# InkTime.net
KiCad netlist of a schematic drawn in EAGLE
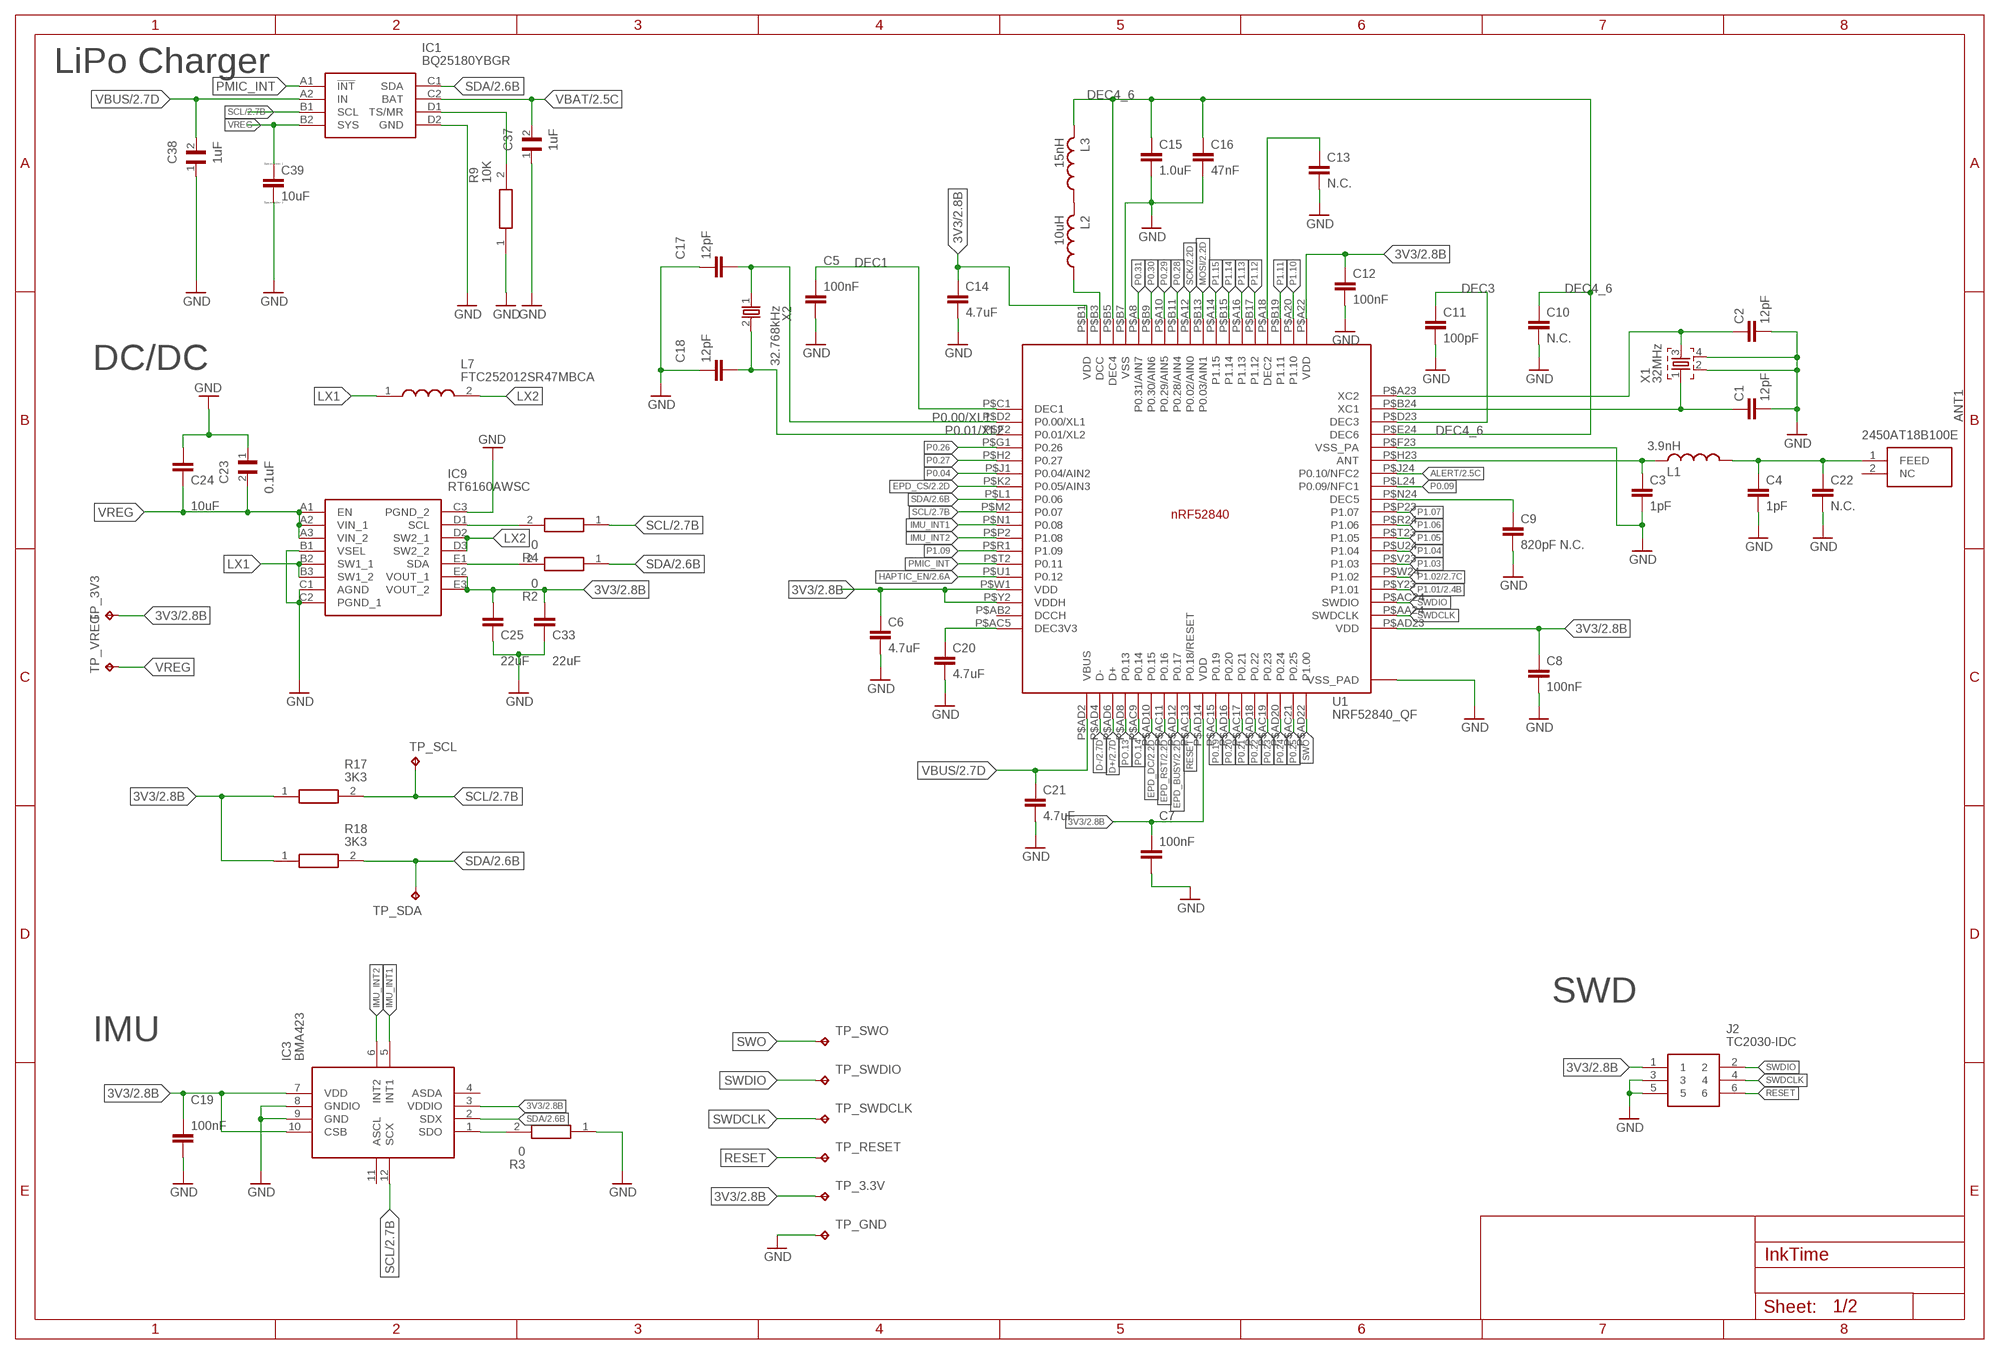
[diagram p0: schematic, sheet 1]
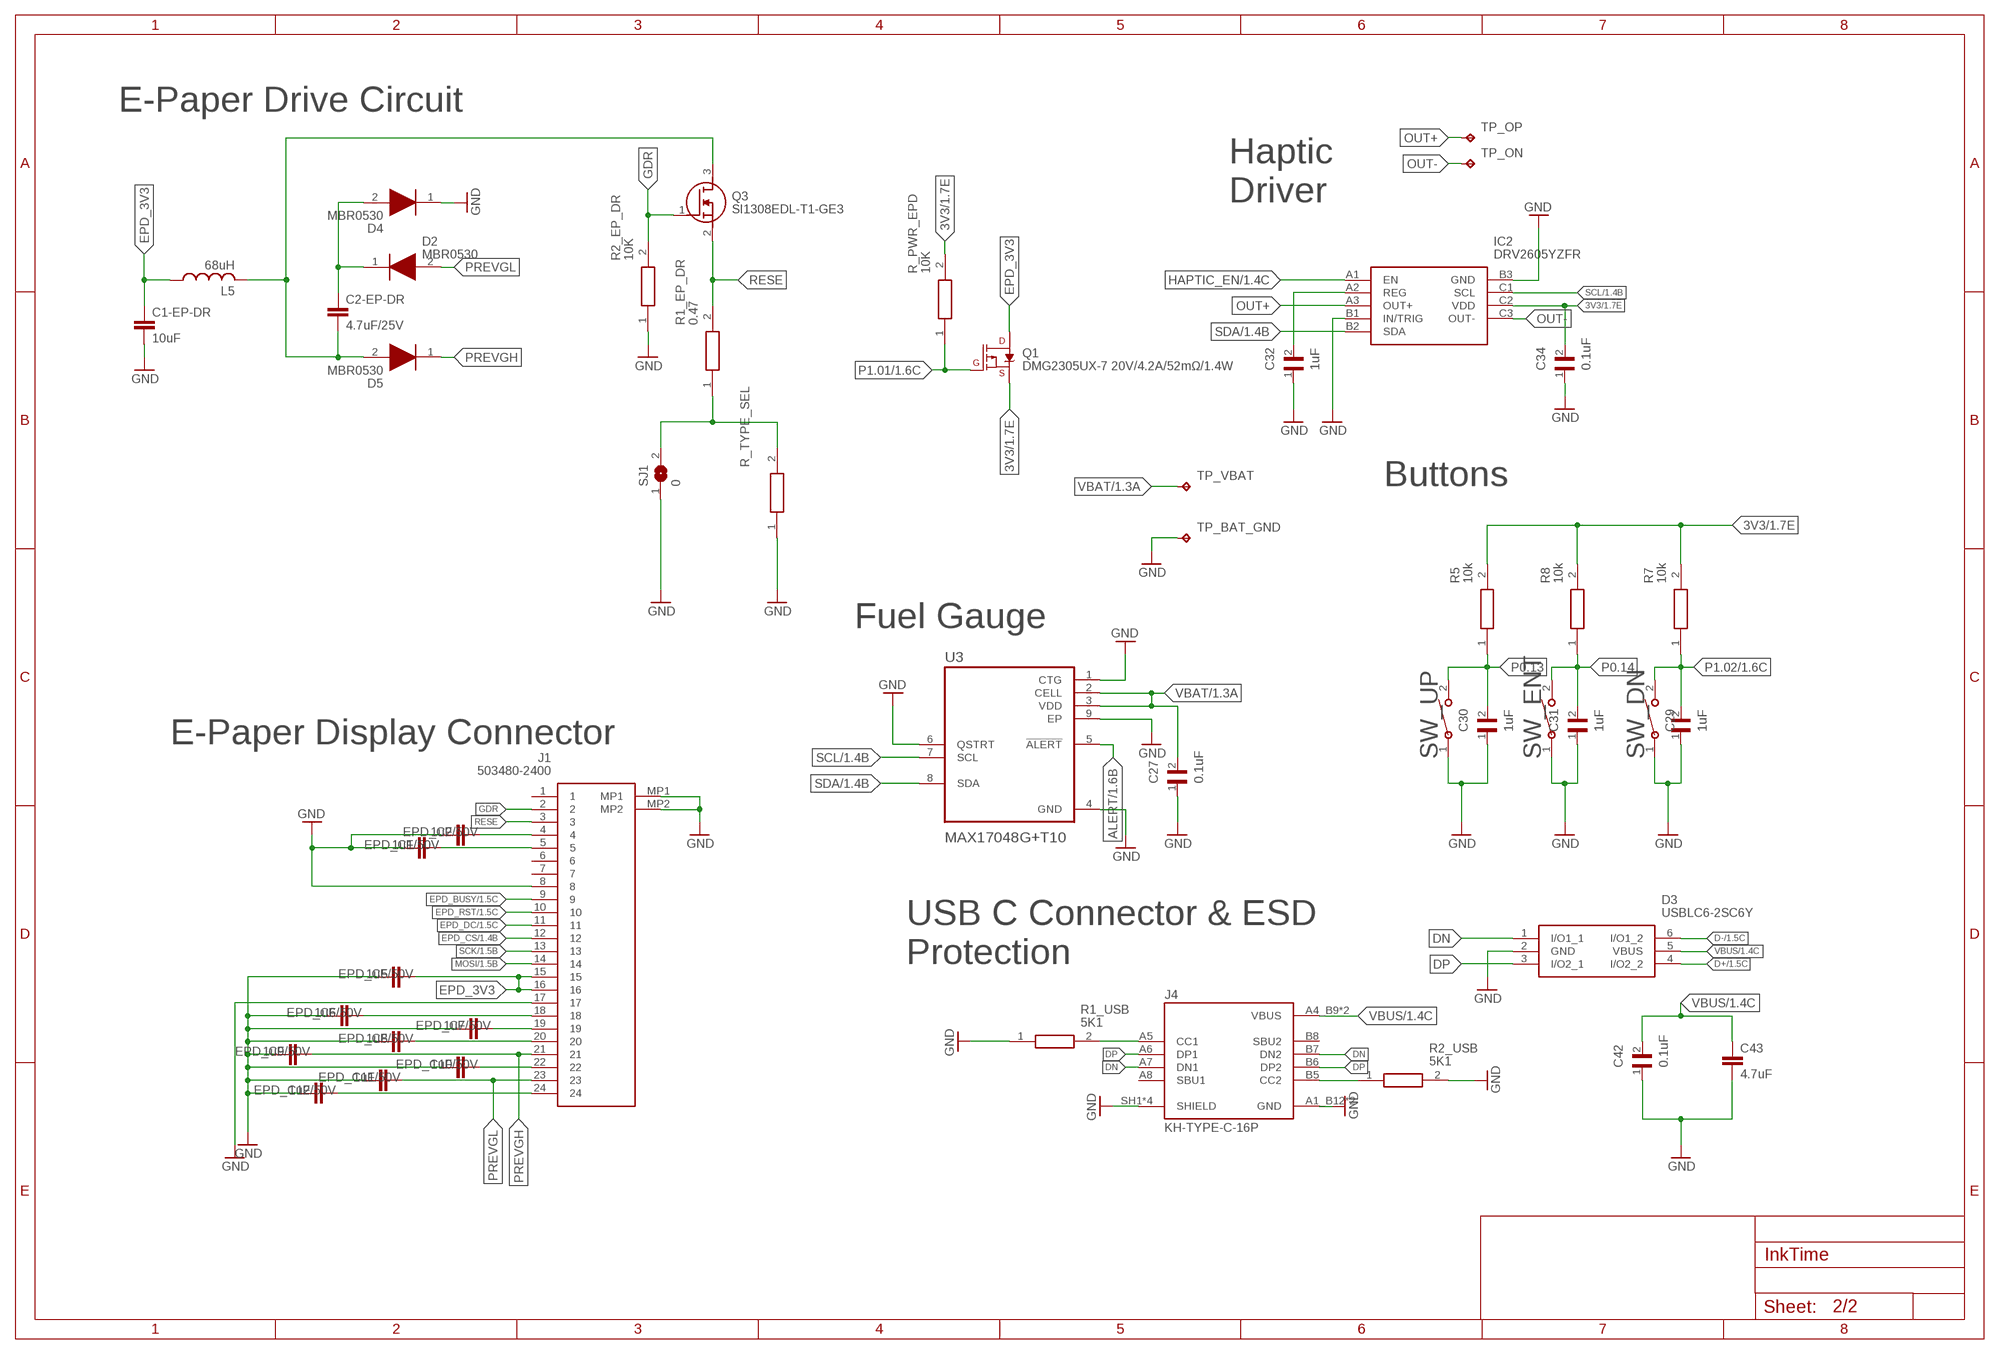
[diagram p1: schematic, sheet 2]

(export (version "E")
  (design (tool "Eeschema 10.0.6"))
  (components
    (comp (ref "ANT1")
      (value "2450AT18B100E")
      (footprint "eagle-import:2450AT18B100E_ANTC3216X140N")
      (fields (field (name "MOUSER_PART_NUMBER") "609-2450AT18B100E"))
      (libsource (lib "eagle-import") (part "2450AT18B100E_2450AT18B100E"))
    )
    (comp (ref "C1")
      (value "12pF")
      (footprint "eagle-import:NORDIC_NRF_3_RESC0201_L")
      (libsource (lib "eagle-import") (part "NORDIC_NRF_3_CAPACITOR_0201_L"))
    )
    (comp (ref "C2")
      (value "12pF")
      (footprint "eagle-import:NORDIC_NRF_3_RESC0201_L")
      (libsource (lib "eagle-import") (part "NORDIC_NRF_3_CAPACITOR_0201_L"))
    )
    (comp (ref "C3")
      (value "1pF")
      (footprint "eagle-import:NORDIC_NRF_3_RESC0201_L")
      (libsource (lib "eagle-import") (part "NORDIC_NRF_3_CAPACITOR_0201_L"))
    )
    (comp (ref "C4")
      (value "1pF")
      (footprint "eagle-import:NORDIC_NRF_3_RESC0201_L")
      (libsource (lib "eagle-import") (part "NORDIC_NRF_3_CAPACITOR_0201_L"))
    )
    (comp (ref "C5")
      (value "100nF")
      (footprint "eagle-import:NORDIC_NRF_3_RESC0201_L")
      (libsource (lib "eagle-import") (part "NORDIC_NRF_3_CAPACITOR_0201_L"))
    )
    (comp (ref "C6")
      (value "4.7uF")
      (footprint "eagle-import:PERFECT_0402_0402")
      (libsource (lib "eagle-import") (part "PERFECT_0402_CAP_0402"))
    )
    (comp (ref "C7")
      (value "100nF")
      (footprint "eagle-import:NORDIC_NRF_3_RESC0201_L")
      (libsource (lib "eagle-import") (part "NORDIC_NRF_3_CAPACITOR_0201_L"))
    )
    (comp (ref "C8")
      (value "100nF")
      (footprint "eagle-import:NORDIC_NRF_3_RESC0201_L")
      (libsource (lib "eagle-import") (part "NORDIC_NRF_3_CAPACITOR_0201_L"))
    )
    (comp (ref "C9")
      (value "820pF N.C.")
      (footprint "eagle-import:NORDIC_NRF_3_RESC0201_L")
      (libsource (lib "eagle-import") (part "NORDIC_NRF_3_CAPACITOR_0201_L"))
    )
    (comp (ref "C10")
      (value "N.C.")
      (footprint "eagle-import:NORDIC_NRF_3_RESC0201_L")
      (libsource (lib "eagle-import") (part "NORDIC_NRF_3_CAPACITOR_0201_L"))
    )
    (comp (ref "C11")
      (value "100pF")
      (footprint "eagle-import:NORDIC_NRF_3_RESC0201_L")
      (libsource (lib "eagle-import") (part "NORDIC_NRF_3_CAPACITOR_0201_L"))
    )
    (comp (ref "C12")
      (value "100nF")
      (footprint "eagle-import:NORDIC_NRF_3_RESC0201_L")
      (libsource (lib "eagle-import") (part "NORDIC_NRF_3_CAPACITOR_0201_L"))
    )
    (comp (ref "C13")
      (value "N.C.")
      (footprint "eagle-import:NORDIC_NRF_3_RESC0201_L")
      (libsource (lib "eagle-import") (part "NORDIC_NRF_3_CAPACITOR_0201_L"))
    )
    (comp (ref "C14")
      (value "4.7uF")
      (footprint "eagle-import:PERFECT_0402_0402")
      (libsource (lib "eagle-import") (part "PERFECT_0402_CAP_0402"))
    )
    (comp (ref "C15")
      (value "1.0uF")
      (footprint "eagle-import:PERFECT_0402_0402")
      (libsource (lib "eagle-import") (part "PERFECT_0402_CAP_0402"))
    )
    (comp (ref "C16")
      (value "47nF")
      (footprint "eagle-import:NORDIC_NRF_3_RESC0201_L")
      (libsource (lib "eagle-import") (part "NORDIC_NRF_3_CAPACITOR_0201_L"))
    )
    (comp (ref "C17")
      (value "12pF")
      (footprint "eagle-import:NORDIC_NRF_3_RESC0201_L")
      (libsource (lib "eagle-import") (part "NORDIC_NRF_3_CAPACITOR_0201_L"))
    )
    (comp (ref "C18")
      (value "12pF")
      (footprint "eagle-import:NORDIC_NRF_3_RESC0201_L")
      (libsource (lib "eagle-import") (part "NORDIC_NRF_3_CAPACITOR_0201_L"))
    )
    (comp (ref "C19")
      (value "100nF")
      (footprint "eagle-import:NORDIC_NRF_3_RESC0201_L")
      (libsource (lib "eagle-import") (part "NORDIC_NRF_3_CAPACITOR_0201_L"))
    )
    (comp (ref "C20")
      (value "4.7uF")
      (footprint "eagle-import:PERFECT_0402_0402")
      (libsource (lib "eagle-import") (part "PERFECT_0402_CAP_0402"))
    )
    (comp (ref "C21")
      (value "4.7uF")
      (footprint "eagle-import:PERFECT_0402_0402")
      (libsource (lib "eagle-import") (part "PERFECT_0402_CAP_0402"))
    )
    (comp (ref "C22")
      (value "N.C.")
      (footprint "eagle-import:NORDIC_NRF_3_RESC0201_L")
      (libsource (lib "eagle-import") (part "NORDIC_NRF_3_CAPACITOR_0201_L"))
    )
    (comp (ref "C23")
      (value "0.1uF")
      (footprint "eagle-import:GRM011R60J152KE01L_1_0201")
      (libsource (lib "eagle-import") (part "GRM011R60J152KE01L_1_GRM011R60J152KE01L"))
    )
    (comp (ref "C24")
      (value "10uF")
      (footprint "eagle-import:PERFECT_0402_0402")
      (libsource (lib "eagle-import") (part "PERFECT_0402_CAP_0402"))
    )
    (comp (ref "C25")
      (value "22uF")
      (footprint "eagle-import:PERFECT_0402_0402")
      (libsource (lib "eagle-import") (part "PERFECT_0402_CAP_0402"))
    )
    (comp (ref "C33")
      (value "22uF")
      (footprint "eagle-import:PERFECT_0402_0402")
      (libsource (lib "eagle-import") (part "PERFECT_0402_CAP_0402"))
    )
    (comp (ref "C37")
      (value "1uF")
      (footprint "eagle-import:GRM011R60J152KE01L_1_0201")
      (libsource (lib "eagle-import") (part "GRM011R60J152KE01L_1_GRM011R60J152KE01L"))
    )
    (comp (ref "C38")
      (value "1uF")
      (footprint "eagle-import:GRM011R60J152KE01L_1_0201")
      (libsource (lib "eagle-import") (part "GRM011R60J152KE01L_1_GRM011R60J152KE01L"))
    )
    (comp (ref "C39")
      (value "10uF")
      (footprint "eagle-import:ESP32_C6_LIBRARY_1_ESP32_WROVER_EAGLE-LTSPICE_C0402")
      (libsource (lib "eagle-import") (part "ESP32_C6_LIBRARY_1_ESP32_WROVER_EAGLE-LTSPICE_CC0402"))
    )
    (comp (ref "IC1")
      (value "BQ25180YBGR")
      (footprint "eagle-import:BQ25180YBGR_BGA8C40P2X4_100X155X50")
      (fields (field (name "MOUSER_PART_NUMBER") "595-BQ25180YBGR"))
      (libsource (lib "eagle-import") (part "BQ25180YBGR_BQ25180YBGR"))
    )
    (comp (ref "IC3")
      (value "BMA423")
      (footprint "eagle-import:BMA423_BMA423")
      (fields (field (name "MOUSER_PART_NUMBER") "262-BMA423"))
      (libsource (lib "eagle-import") (part "BMA423_BMA423"))
    )
    (comp (ref "IC9")
      (value "RT6160AWSC")
      (footprint "eagle-import:RT6160AWSC_BGA15C40P3X5_140X230X60")
      (fields (field (name "MOUSER_PART_NUMBER") "835-RT6160AWSC"))
      (libsource (lib "eagle-import") (part "RT6160AWSC_RT6160AWSC"))
    )
    (comp (ref "J2")
      (value "TC2030-IDC")
      (footprint "eagle-import:TC2030-IDC_TC2030IDC")
      (libsource (lib "eagle-import") (part "TC2030-IDC_TC2030-IDC"))
    )
    (comp (ref "L1")
      (value "3.9nH")
      (footprint "eagle-import:NORDIC_NRF_2_RESC0402_L")
      (libsource (lib "eagle-import") (part "NORDIC_NRF_2_INDUCTOR_0402_L"))
    )
    (comp (ref "L2")
      (value "10uH")
      (footprint "eagle-import:NORDIC_NRF_2_RESC0402_L")
      (libsource (lib "eagle-import") (part "NORDIC_NRF_2_INDUCTOR_0402_L"))
    )
    (comp (ref "L3")
      (value "15nH")
      (footprint "eagle-import:NORDIC_NRF_2_RESC0402_L")
      (libsource (lib "eagle-import") (part "NORDIC_NRF_2_INDUCTOR_0402_L"))
    )
    (comp (ref "L7")
      (value "FTC252012SR47MBCA")
      (footprint "eagle-import:MLP2016SR47MT0S1_INDC2016X100N")
      (libsource (lib "eagle-import") (part "MLP2016SR47MT0S1_FTC252012SR47MBCA"))
    )
    (comp (ref "R2")
      (value "0")
      (footprint "eagle-import:ERA-1AEB3401C_0201")
      (libsource (lib "eagle-import") (part "ERA-1AEB3401C_CPF0201D7K68C1"))
    )
    (comp (ref "R3")
      (value "0")
      (footprint "eagle-import:CPF0201D7K68C1_0201")
      (libsource (lib "eagle-import") (part "CPF0201D7K68C1_CPF0201D7K68C1"))
    )
    (comp (ref "R4")
      (value "0")
      (footprint "eagle-import:ERA-1AEB3401C_0201")
      (libsource (lib "eagle-import") (part "ERA-1AEB3401C_CPF0201D7K68C1"))
    )
    (comp (ref "R9")
      (value "10K")
      (footprint "eagle-import:ERA-1AEB3401C_0201")
      (libsource (lib "eagle-import") (part "ERA-1AEB3401C_CPF0201D7K68C1"))
    )
    (comp (ref "R17")
      (value "3K3")
      (footprint "eagle-import:ERA-1AEB3401C_0201")
      (libsource (lib "eagle-import") (part "ERA-1AEB3401C_CPF0201D7K68C1"))
    )
    (comp (ref "R18")
      (value "3K3")
      (footprint "eagle-import:ERA-1AEB3401C_0201")
      (libsource (lib "eagle-import") (part "ERA-1AEB3401C_CPF0201D7K68C1"))
    )
    (comp (ref "TP_3.3V")
      (value "HECTOR_WATCH_1_TPTP20R")
      (footprint "eagle-import:HECTOR_WATCH_1_TP20R")
      (libsource (lib "eagle-import") (part "HECTOR_WATCH_1_TPTP20R"))
    )
    (comp (ref "TP_3V3")
      (value "HECTOR_WATCH_1_TPTP20R")
      (footprint "eagle-import:HECTOR_WATCH_1_TP20R")
      (libsource (lib "eagle-import") (part "HECTOR_WATCH_1_TPTP20R"))
    )
    (comp (ref "TP_GND")
      (value "HECTOR_WATCH_1_TPTP20R")
      (footprint "eagle-import:HECTOR_WATCH_1_TP20R")
      (libsource (lib "eagle-import") (part "HECTOR_WATCH_1_TPTP20R"))
    )
    (comp (ref "TP_RESET")
      (value "HECTOR_WATCH_1_TPTP20R")
      (footprint "eagle-import:HECTOR_WATCH_1_TP20R")
      (libsource (lib "eagle-import") (part "HECTOR_WATCH_1_TPTP20R"))
    )
    (comp (ref "TP_SCL")
      (value "HECTOR_WATCH_1_TPTP20R")
      (footprint "eagle-import:HECTOR_WATCH_1_TP20R")
      (libsource (lib "eagle-import") (part "HECTOR_WATCH_1_TPTP20R"))
    )
    (comp (ref "TP_SDA")
      (value "HECTOR_WATCH_1_TPTP20R")
      (footprint "eagle-import:HECTOR_WATCH_1_TP20R")
      (libsource (lib "eagle-import") (part "HECTOR_WATCH_1_TPTP20R"))
    )
    (comp (ref "TP_SWDCLK")
      (value "HECTOR_WATCH_1_TPTP20R")
      (footprint "eagle-import:HECTOR_WATCH_1_TP20R")
      (libsource (lib "eagle-import") (part "HECTOR_WATCH_1_TPTP20R"))
    )
    (comp (ref "TP_SWDIO")
      (value "HECTOR_WATCH_1_TPTP20R")
      (footprint "eagle-import:HECTOR_WATCH_1_TP20R")
      (libsource (lib "eagle-import") (part "HECTOR_WATCH_1_TPTP20R"))
    )
    (comp (ref "TP_SWO")
      (value "HECTOR_WATCH_1_TPTP20R")
      (footprint "eagle-import:HECTOR_WATCH_1_TP20R")
      (libsource (lib "eagle-import") (part "HECTOR_WATCH_1_TPTP20R"))
    )
    (comp (ref "TP_VREG")
      (value "HECTOR_WATCH_1_TPTP20R")
      (footprint "eagle-import:HECTOR_WATCH_1_TP20R")
      (libsource (lib "eagle-import") (part "HECTOR_WATCH_1_TPTP20R"))
    )
    (comp (ref "U1")
      (value "NRF52840_QF")
      (footprint "eagle-import:NORDIC_NRF_4_AQFN50P700X700X85_HS-74N")
      (libsource (lib "eagle-import") (part "NORDIC_NRF_4_NRF52840_QF"))
    )
    (comp (ref "X1")
      (value "32MHz")
      (footprint "eagle-import:NORDIC_NRF_BT-XTAL_2016_N")
      (libsource (lib "eagle-import") (part "NORDIC_NRF_XTAL_32MHZ"))
    )
    (comp (ref "X2")
      (value "32.768kHz")
      (footprint "eagle-import:NORDIC_NRF_1_XTAL_3215_N")
      (libsource (lib "eagle-import") (part "NORDIC_NRF_1_XTAL_32KHZ"))
    )
    (comp (ref "C1-EP-DR")
      (value "10uF")
      (footprint "eagle-import:PERFECT_0402_0402")
      (libsource (lib "eagle-import") (part "PERFECT_0402_CAP_0402"))
    )
    (comp (ref "C2-EP-DR")
      (value "4.7uF/25V")
      (footprint "eagle-import:PERFECT_0402_0402")
      (libsource (lib "eagle-import") (part "PERFECT_0402_CAP_0402"))
    )
    (comp (ref "C27")
      (value "0.1uF")
      (footprint "eagle-import:GRM011R60J152KE01L_2_CAPC0201X13N")
      (fields (field (name "MF") "Murata") (field (name "MP") "GRM011R60J152KE01L"))
      (libsource (lib "eagle-import") (part "GRM011R60J152KE01L_2_GRM011R60J152KE01L"))
    )
    (comp (ref "C29")
      (value "1uF")
      (footprint "eagle-import:GRM011R60J152KE01L_2_CAPC0201X13N")
      (fields (field (name "MF") "Murata") (field (name "MP") "GRM011R60J152KE01L"))
      (libsource (lib "eagle-import") (part "GRM011R60J152KE01L_2_GRM011R60J152KE01L"))
    )
    (comp (ref "C30")
      (value "1uF")
      (footprint "eagle-import:GRM011R60J152KE01L_2_CAPC0201X13N")
      (fields (field (name "MF") "Murata") (field (name "MP") "GRM011R60J152KE01L"))
      (libsource (lib "eagle-import") (part "GRM011R60J152KE01L_2_GRM011R60J152KE01L"))
    )
    (comp (ref "C31")
      (value "1uF")
      (footprint "eagle-import:GRM011R60J152KE01L_2_CAPC0201X13N")
      (fields (field (name "MF") "Murata") (field (name "MP") "GRM011R60J152KE01L"))
      (libsource (lib "eagle-import") (part "GRM011R60J152KE01L_2_GRM011R60J152KE01L"))
    )
    (comp (ref "C32")
      (value "1uF")
      (footprint "eagle-import:GRM011R60J152KE01L_2_CAPC0201X13N")
      (fields (field (name "MF") "Murata") (field (name "MP") "GRM011R60J152KE01L"))
      (libsource (lib "eagle-import") (part "GRM011R60J152KE01L_2_GRM011R60J152KE01L"))
    )
    (comp (ref "C34")
      (value "0.1uF")
      (footprint "eagle-import:GRM011R60J152KE01L_2_CAPC0201X13N")
      (fields (field (name "MF") "Murata") (field (name "MP") "GRM011R60J152KE01L"))
      (libsource (lib "eagle-import") (part "GRM011R60J152KE01L_2_GRM011R60J152KE01L"))
    )
    (comp (ref "C42")
      (value "0.1uF")
      (footprint "eagle-import:GRM011R60J152KE01L_2_CAPC0201X13N")
      (fields (field (name "MF") "Murata") (field (name "MP") "GRM011R60J152KE01L"))
      (libsource (lib "eagle-import") (part "GRM011R60J152KE01L_2_GRM011R60J152KE01L"))
    )
    (comp (ref "C43")
      (value "4.7uF")
      (footprint "eagle-import:PERFECT_0402_0402")
      (libsource (lib "eagle-import") (part "PERFECT_0402_CAP_0402"))
    )
    (comp (ref "D2")
      (value "MBR0530")
      (footprint "eagle-import:ESP32_C6_LIBRARY_5_SOD3716X135N")
      (fields (field (name "MF") "ON Semiconductor"))
      (libsource (lib "eagle-import") (part "ESP32_C6_LIBRARY_5_MBR0530"))
    )
    (comp (ref "D3")
      (value "USBLC6-2SC6Y")
      (footprint "eagle-import:ESP32_C6_LIBRARY_3_SOT95P280X145-6N")
      (fields (field (name "MF") "STMicroelectronics"))
      (libsource (lib "eagle-import") (part "ESP32_C6_LIBRARY_3_USBLC6-2SC6Y"))
    )
    (comp (ref "D4")
      (value "MBR0530")
      (footprint "eagle-import:ESP32_C6_LIBRARY_5_SOD3716X135N")
      (fields (field (name "MF") "ON Semiconductor"))
      (libsource (lib "eagle-import") (part "ESP32_C6_LIBRARY_5_MBR0530"))
    )
    (comp (ref "D5")
      (value "MBR0530")
      (footprint "eagle-import:ESP32_C6_LIBRARY_5_SOD3716X135N")
      (fields (field (name "MF") "ON Semiconductor"))
      (libsource (lib "eagle-import") (part "ESP32_C6_LIBRARY_5_MBR0530"))
    )
    (comp (ref "EPD_C1")
      (value "1uF/50V")
      (footprint "eagle-import:PERFECT_0402_0402")
      (libsource (lib "eagle-import") (part "PERFECT_0402_CAP_0402"))
    )
    (comp (ref "EPD_C2")
      (value "1uF/50V")
      (footprint "eagle-import:PERFECT_0402_0402")
      (libsource (lib "eagle-import") (part "PERFECT_0402_CAP_0402"))
    )
    (comp (ref "EPD_C5")
      (value "1uF/50V")
      (footprint "eagle-import:PERFECT_0402_0402")
      (libsource (lib "eagle-import") (part "PERFECT_0402_CAP_0402"))
    )
    (comp (ref "EPD_C6")
      (value "1uF/50V")
      (footprint "eagle-import:PERFECT_0402_0402")
      (libsource (lib "eagle-import") (part "PERFECT_0402_CAP_0402"))
    )
    (comp (ref "EPD_C7")
      (value "1uF/50V")
      (footprint "eagle-import:PERFECT_0402_0402")
      (libsource (lib "eagle-import") (part "PERFECT_0402_CAP_0402"))
    )
    (comp (ref "EPD_C8")
      (value "1uF/50V")
      (footprint "eagle-import:PERFECT_0402_0402")
      (libsource (lib "eagle-import") (part "PERFECT_0402_CAP_0402"))
    )
    (comp (ref "EPD_C9")
      (value "1uF/50V")
      (footprint "eagle-import:PERFECT_0402_0402")
      (libsource (lib "eagle-import") (part "PERFECT_0402_CAP_0402"))
    )
    (comp (ref "EPD_C10")
      (value "1uF/50V")
      (footprint "eagle-import:PERFECT_0402_0402")
      (libsource (lib "eagle-import") (part "PERFECT_0402_CAP_0402"))
    )
    (comp (ref "EPD_C11")
      (value "1uF/50V")
      (footprint "eagle-import:PERFECT_0402_0402")
      (libsource (lib "eagle-import") (part "PERFECT_0402_CAP_0402"))
    )
    (comp (ref "EPD_C12")
      (value "1uF/50V")
      (footprint "eagle-import:PERFECT_0402_0402")
      (libsource (lib "eagle-import") (part "PERFECT_0402_CAP_0402"))
    )
    (comp (ref "IC2")
      (value "DRV2605YZFR")
      (footprint "eagle-import:DRV2605YZFR_BGA9C50P3X3_144X144X62")
      (libsource (lib "eagle-import") (part "DRV2605YZFR_DRV2605YZFR"))
    )
    (comp (ref "J1")
      (value "503480-2400")
      (footprint "eagle-import:503480-2400_5034802400")
      (fields (field (name "MOUSER_PART_NUMBER") "538-503480-2400"))
      (libsource (lib "eagle-import") (part "503480-2400_503480-2400"))
    )
    (comp (ref "J4")
      (value "KH-TYPE-C-16P")
      (footprint "eagle-import:KH-TYPE-C-16P_KINGHELM_KH-TYPE-C-16P")
      (fields (field (name "MF") "kinghelm"))
      (libsource (lib "eagle-import") (part "KH-TYPE-C-16P_KH-TYPE-C-16P"))
    )
    (comp (ref "L5")
      (value "68uH")
      (footprint "eagle-import:NORDIC_NRF_2_RESC0402_L")
      (libsource (lib "eagle-import") (part "NORDIC_NRF_2_INDUCTOR_0402_L"))
    )
    (comp (ref "Q1")
      (value "DMG2305UX-7 20V/4.2A/52mΩ/1.4W")
      (footprint "eagle-import:ESP32_C6_LIBRARY_4_ESP32_C6_LIBRARY_4_ESP32_C6_LIBRARY_4_ESP32_C6_LIBRARY_4_ESP32_WROVER_SPARKFUN-DISCRETESEMI_SOT23-3")
      (libsource (lib "eagle-import") (part "ESP32_C6_LIBRARY_4_ESP32_WROVER_SPARKFUN-DISCRETESEMI_MOSFET_PCH-DMG2305UX-7"))
    )
    (comp (ref "Q3")
      (value "SI1308EDL-T1-GE3")
      (footprint "eagle-import:ESP32_C6_LIBRARY_6_SOT65P210X110-3N")
      (fields (field (name "MF") "Vishay Siliconix"))
      (libsource (lib "eagle-import") (part "ESP32_C6_LIBRARY_6_SI1308EDL-T1-GE3"))
    )
    (comp (ref "R1_EP_DR")
      (value "0.47")
      (footprint "eagle-import:ERA-1AEB3401C_0201")
      (libsource (lib "eagle-import") (part "ERA-1AEB3401C_CPF0201D7K68C1"))
    )
    (comp (ref "R1_USB")
      (value "5K1")
      (footprint "eagle-import:CPF0201D7K68C1_0201")
      (libsource (lib "eagle-import") (part "CPF0201D7K68C1_CPF0201D7K68C1"))
    )
    (comp (ref "R2_EP_DR")
      (value "10K")
      (footprint "eagle-import:ERA-1AEB3401C_0201")
      (libsource (lib "eagle-import") (part "ERA-1AEB3401C_CPF0201D7K68C1"))
    )
    (comp (ref "R2_USB")
      (value "5K1")
      (footprint "eagle-import:CPF0201D7K68C1_0201")
      (libsource (lib "eagle-import") (part "CPF0201D7K68C1_CPF0201D7K68C1"))
    )
    (comp (ref "R5")
      (value "10k")
      (footprint "eagle-import:CPF0201D7K68C1_0201")
      (libsource (lib "eagle-import") (part "CPF0201D7K68C1_CPF0201D7K68C1"))
    )
    (comp (ref "R7")
      (value "10k")
      (footprint "eagle-import:CPF0201D7K68C1_0201")
      (libsource (lib "eagle-import") (part "CPF0201D7K68C1_CPF0201D7K68C1"))
    )
    (comp (ref "R8")
      (value "10k")
      (footprint "eagle-import:CPF0201D7K68C1_0201")
      (libsource (lib "eagle-import") (part "CPF0201D7K68C1_CPF0201D7K68C1"))
    )
    (comp (ref "R_PWR_EPD")
      (value "10K")
      (footprint "eagle-import:CPF0201D7K68C1_0201")
      (libsource (lib "eagle-import") (part "CPF0201D7K68C1_CPF0201D7K68C1"))
    )
    (comp (ref "R_TYPE_SEL")
      (value "2.2")
      (footprint "eagle-import:ERA-1AEB3401C_0201")
      (libsource (lib "eagle-import") (part "ERA-1AEB3401C_CPF0201D7K68C1"))
    )
    (comp (ref "SJ1")
      (value "0")
      (footprint "eagle-import:ESP32_C6_LIBRARY_7_JUMPER_SJ")
      (libsource (lib "eagle-import") (part "ESP32_C6_LIBRARY_7_JUMPER_SJ"))
    )
    (comp (ref "SW_DN")
      (value "2025-10-22_07-23-44_LIBRARY_EVP-AKE31ASW_EVP-AKE31A_PAN")
      (footprint "eagle-import:2025-10-22_07-23-44_LIBRARY_SW_EVP-AKE31A_PAN")
      (fields
        (field (name "MANUFACTURER_PART_NUMBER") "EVP-AKE31A")
        (field (name "COPYRIGHT") "Copyright (C) 2025 Ultra Librarian. All rights reserved.")
      )
      (libsource (lib "eagle-import") (part "2025-10-22_07-23-44_LIBRARY_EVP-AKE31ASW_EVP-AKE31A_PAN"))
    )
    (comp (ref "SW_ENT")
      (value "2025-10-22_07-23-44_LIBRARY_EVP-AKE31ASW_EVP-AKE31A_PAN")
      (footprint "eagle-import:2025-10-22_07-23-44_LIBRARY_SW_EVP-AKE31A_PAN")
      (fields
        (field (name "MANUFACTURER_PART_NUMBER") "EVP-AKE31A")
        (field (name "COPYRIGHT") "Copyright (C) 2025 Ultra Librarian. All rights reserved.")
      )
      (libsource (lib "eagle-import") (part "2025-10-22_07-23-44_LIBRARY_EVP-AKE31ASW_EVP-AKE31A_PAN"))
    )
    (comp (ref "SW_UP")
      (value "2025-10-22_07-23-44_LIBRARY_EVP-AKE31ASW_EVP-AKE31A_PAN")
      (footprint "eagle-import:2025-10-22_07-23-44_LIBRARY_SW_EVP-AKE31A_PAN")
      (fields
        (field (name "MANUFACTURER_PART_NUMBER") "EVP-AKE31A")
        (field (name "COPYRIGHT") "Copyright (C) 2025 Ultra Librarian. All rights reserved.")
      )
      (libsource (lib "eagle-import") (part "2025-10-22_07-23-44_LIBRARY_EVP-AKE31ASW_EVP-AKE31A_PAN"))
    )
    (comp (ref "TP_BAT_GND")
      (value "HECTOR_WATCH_1_TPTP20R")
      (footprint "eagle-import:HECTOR_WATCH_1_TP20R")
      (libsource (lib "eagle-import") (part "HECTOR_WATCH_1_TPTP20R"))
    )
    (comp (ref "TP_ON")
      (value "HECTOR_WATCH_1_TPTP20R")
      (footprint "eagle-import:HECTOR_WATCH_1_TP20R")
      (libsource (lib "eagle-import") (part "HECTOR_WATCH_1_TPTP20R"))
    )
    (comp (ref "TP_OP")
      (value "HECTOR_WATCH_1_TPTP20R")
      (footprint "eagle-import:HECTOR_WATCH_1_TP20R")
      (libsource (lib "eagle-import") (part "HECTOR_WATCH_1_TPTP20R"))
    )
    (comp (ref "TP_VBAT")
      (value "HECTOR_WATCH_1_TPTP20R")
      (footprint "eagle-import:HECTOR_WATCH_1_TP20R")
      (libsource (lib "eagle-import") (part "HECTOR_WATCH_1_TPTP20R"))
    )
    (comp (ref "U3")
      (value "MAX17048G+T10")
      (footprint "eagle-import:ESP32_C6_LIBRARY_SON50P200X200X80-9N")
      (fields (field (name "MF") "Analog Devices"))
      (libsource (lib "eagle-import") (part "ESP32_C6_LIBRARY_MAX17048G+T10"))
    )
  )
  (nets
    (net (code "1") (name "3V3") (class "Default")
      (node (ref "C12") (pin "1") (pinfunction "1_1") (pintype "passive"))
      (node (ref "C14") (pin "1") (pinfunction "1_1") (pintype "passive"))
      (node (ref "C19") (pin "1") (pinfunction "1_1") (pintype "passive"))
      (node (ref "C25") (pin "1") (pinfunction "1_1") (pintype "passive"))
      (node (ref "C33") (pin "1") (pinfunction "1_1") (pintype "passive"))
      (node (ref "C34") (pin "2") (pinfunction "2_2") (pintype "passive"))
      (node (ref "C6") (pin "1") (pinfunction "1_1") (pintype "passive"))
      (node (ref "C7") (pin "1") (pinfunction "1_1") (pintype "passive"))
      (node (ref "C8") (pin "1") (pinfunction "1_1") (pintype "passive"))
      (node (ref "IC2") (pin "C2") (pinfunction "VDD_C2") (pintype "bidirectional"))
      (node (ref "IC3") (pin "10") (pinfunction "CSB_10") (pintype "bidirectional"))
      (node (ref "IC3") (pin "3") (pinfunction "VDDIO_3") (pintype "bidirectional"))
      (node (ref "IC3") (pin "7") (pinfunction "VDD_7") (pintype "bidirectional"))
      (node (ref "IC9") (pin "E2") (pinfunction "VOUT_1_E2") (pintype "bidirectional"))
      (node (ref "IC9") (pin "E3") (pinfunction "VOUT_2_E3") (pintype "bidirectional"))
      (node (ref "J2") (pin "1") (pinfunction "1_1") (pintype "bidirectional"))
      (node (ref "Q1") (pin "2") (pinfunction "S_2") (pintype "bidirectional"))
      (node (ref "R17") (pin "1") (pinfunction "1_1") (pintype "bidirectional"))
      (node (ref "R18") (pin "1") (pinfunction "1_1") (pintype "bidirectional"))
      (node (ref "R5") (pin "2") (pinfunction "2_2") (pintype "bidirectional"))
      (node (ref "R7") (pin "2") (pinfunction "2_2") (pintype "bidirectional"))
      (node (ref "R8") (pin "2") (pinfunction "2_2") (pintype "bidirectional"))
      (node (ref "R_PWR_EPD") (pin "2") (pinfunction "2_2") (pintype "bidirectional"))
      (node (ref "TP_3.3V") (pin "TP") (pinfunction "TP_TP") (pintype "input"))
      (node (ref "TP_3V3") (pin "TP") (pinfunction "TP_TP") (pintype "input"))
      (node (ref "U1") (pin "P$A22") (pinfunction "VDD_P$A22") (pintype "power_in"))
      (node (ref "U1") (pin "P$AD14") (pinfunction "VDD_P$AD14") (pintype "power_in"))
      (node (ref "U1") (pin "P$AD23") (pinfunction "VDD_P$AD23") (pintype "power_in"))
      (node (ref "U1") (pin "P$B1") (pinfunction "VDD_P$B1") (pintype "power_in"))
      (node (ref "U1") (pin "P$W1") (pinfunction "VDD_P$W1") (pintype "power_in"))
      (node (ref "U1") (pin "P$Y2") (pinfunction "VDDH_P$Y2") (pintype "power_in"))
    )
    (net (code "2") (name "ALERT") (class "Default")
      (node (ref "U1") (pin "P$J24") (pinfunction "P0.10/NFC2_P$J24") (pintype "bidirectional"))
      (node (ref "U3") (pin "5") (pinfunction "~{ALERT}_5") (pintype "output"))
    )
    (net (code "3") (name "D+") (class "Default")
      (node (ref "D3") (pin "4") (pinfunction "I/O2_2_4") (pintype "bidirectional"))
      (node (ref "U1") (pin "P$AD6") (pinfunction "D+_P$AD6") (pintype "bidirectional"))
    )
    (net (code "4") (name "D-") (class "Default")
      (node (ref "D3") (pin "6") (pinfunction "I/O1_2_6") (pintype "bidirectional"))
      (node (ref "U1") (pin "P$AD4") (pinfunction "D-_P$AD4") (pintype "bidirectional"))
    )
    (net (code "5") (name "DEC1") (class "Default")
      (node (ref "C5") (pin "1") (pinfunction "1_1") (pintype "passive"))
      (node (ref "U1") (pin "P$C1") (pinfunction "DEC1_P$C1") (pintype "power_in"))
    )
    (net (code "6") (name "DEC3") (class "Default")
      (node (ref "C11") (pin "1") (pinfunction "1_1") (pintype "passive"))
      (node (ref "U1") (pin "P$D23") (pinfunction "DEC3_P$D23") (pintype "bidirectional"))
    )
    (net (code "7") (name "DEC4_6") (class "Default")
      (node (ref "C10") (pin "1") (pinfunction "1_1") (pintype "passive"))
      (node (ref "C15") (pin "1") (pinfunction "1_1") (pintype "passive"))
      (node (ref "C16") (pin "1") (pinfunction "1_1") (pintype "passive"))
      (node (ref "L3") (pin "2") (pinfunction "2_2") (pintype "passive"))
      (node (ref "U1") (pin "P$B5") (pinfunction "DEC4_P$B5") (pintype "power_in"))
      (node (ref "U1") (pin "P$E24") (pinfunction "DEC6_P$E24") (pintype "bidirectional"))
    )
    (net (code "8") (name "DN") (class "Default")
      (node (ref "D3") (pin "1") (pinfunction "I/O1_1_1") (pintype "bidirectional"))
      (node (ref "J4") (pin "A7") (pinfunction "DN1_A7") (pintype "bidirectional"))
      (node (ref "J4") (pin "B7") (pinfunction "DN2_B7") (pintype "bidirectional"))
    )
    (net (code "9") (name "DP") (class "Default")
      (node (ref "D3") (pin "3") (pinfunction "I/O2_1_3") (pintype "bidirectional"))
      (node (ref "J4") (pin "A6") (pinfunction "DP1_A6") (pintype "bidirectional"))
      (node (ref "J4") (pin "B6") (pinfunction "DP2_B6") (pintype "bidirectional"))
    )
    (net (code "10") (name "EPD_3V3") (class "Default")
      (node (ref "C1-EP-DR") (pin "1") (pinfunction "1_1") (pintype "passive"))
      (node (ref "EPD_C5") (pin "2") (pinfunction "2_2") (pintype "passive"))
      (node (ref "J1") (pin "15") (pinfunction "15_15") (pintype "bidirectional"))
      (node (ref "J1") (pin "16") (pinfunction "16_16") (pintype "bidirectional"))
      (node (ref "L5") (pin "1") (pinfunction "1_1") (pintype "passive"))
      (node (ref "Q1") (pin "3") (pinfunction "D_3") (pintype "bidirectional"))
    )
    (net (code "11") (name "EPD_BUSY") (class "Default")
      (node (ref "J1") (pin "9") (pinfunction "9_9") (pintype "bidirectional"))
      (node (ref "U1") (pin "P$AD12") (pinfunction "P0.17_P$AD12") (pintype "bidirectional"))
    )
    (net (code "12") (name "EPD_CS") (class "Default")
      (node (ref "J1") (pin "12") (pinfunction "12_12") (pintype "bidirectional"))
      (node (ref "U1") (pin "P$K2") (pinfunction "P0.05/AIN3_P$K2") (pintype "bidirectional"))
    )
    (net (code "13") (name "EPD_DC") (class "Default")
      (node (ref "J1") (pin "11") (pinfunction "11_11") (pintype "bidirectional"))
      (node (ref "U1") (pin "P$AD10") (pinfunction "P0.15_P$AD10") (pintype "bidirectional"))
    )
    (net (code "14") (name "EPD_RST") (class "Default")
      (node (ref "J1") (pin "10") (pinfunction "10_10") (pintype "bidirectional"))
      (node (ref "U1") (pin "P$AC11") (pinfunction "P0.16_P$AC11") (pintype "bidirectional"))
    )
    (net (code "15") (name "GDR") (class "Default")
      (node (ref "J1") (pin "2") (pinfunction "2_2") (pintype "bidirectional"))
      (node (ref "Q3") (pin "1") (pinfunction "G_1") (pintype "bidirectional"))
      (node (ref "R2_EP_DR") (pin "2") (pinfunction "2_2") (pintype "bidirectional"))
    )
    (net (code "16") (name "GND") (class "Default")
      (node (ref "C1") (pin "2") (pinfunction "2_2") (pintype "passive"))
      (node (ref "C1-EP-DR") (pin "2") (pinfunction "2_2") (pintype "passive"))
      (node (ref "C10") (pin "2") (pinfunction "2_2") (pintype "passive"))
      (node (ref "C11") (pin "2") (pinfunction "2_2") (pintype "passive"))
      (node (ref "C12") (pin "2") (pinfunction "2_2") (pintype "passive"))
      (node (ref "C13") (pin "2") (pinfunction "2_2") (pintype "passive"))
      (node (ref "C14") (pin "2") (pinfunction "2_2") (pintype "passive"))
      (node (ref "C15") (pin "2") (pinfunction "2_2") (pintype "passive"))
      (node (ref "C16") (pin "2") (pinfunction "2_2") (pintype "passive"))
      (node (ref "C17") (pin "1") (pinfunction "1_1") (pintype "passive"))
      (node (ref "C18") (pin "1") (pinfunction "1_1") (pintype "passive"))
      (node (ref "C19") (pin "2") (pinfunction "2_2") (pintype "passive"))
      (node (ref "C2") (pin "2") (pinfunction "2_2") (pintype "passive"))
      (node (ref "C20") (pin "2") (pinfunction "2_2") (pintype "passive"))
      (node (ref "C21") (pin "2") (pinfunction "2_2") (pintype "passive"))
      (node (ref "C22") (pin "2") (pinfunction "2_2") (pintype "passive"))
      (node (ref "C23") (pin "1") (pinfunction "1_1") (pintype "passive"))
      (node (ref "C24") (pin "1") (pinfunction "1_1") (pintype "passive"))
      (node (ref "C25") (pin "2") (pinfunction "2_2") (pintype "passive"))
      (node (ref "C27") (pin "1") (pinfunction "1_1") (pintype "passive"))
      (node (ref "C29") (pin "1") (pinfunction "1_1") (pintype "passive"))
      (node (ref "C3") (pin "2") (pinfunction "2_2") (pintype "passive"))
      (node (ref "C30") (pin "1") (pinfunction "1_1") (pintype "passive"))
      (node (ref "C31") (pin "1") (pinfunction "1_1") (pintype "passive"))
      (node (ref "C32") (pin "1") (pinfunction "1_1") (pintype "passive"))
      (node (ref "C33") (pin "2") (pinfunction "2_2") (pintype "passive"))
      (node (ref "C34") (pin "1") (pinfunction "1_1") (pintype "passive"))
      (node (ref "C37") (pin "1") (pinfunction "1_1") (pintype "passive"))
      (node (ref "C38") (pin "1") (pinfunction "1_1") (pintype "passive"))
      (node (ref "C39") (pin "2") (pinfunction "2_2") (pintype "passive"))
      (node (ref "C4") (pin "2") (pinfunction "2_2") (pintype "passive"))
      (node (ref "C42") (pin "1") (pinfunction "1_1") (pintype "passive"))
      (node (ref "C43") (pin "2") (pinfunction "2_2") (pintype "passive"))
      (node (ref "C5") (pin "2") (pinfunction "2_2") (pintype "passive"))
      (node (ref "C6") (pin "2") (pinfunction "2_2") (pintype "passive"))
      (node (ref "C7") (pin "2") (pinfunction "2_2") (pintype "passive"))
      (node (ref "C8") (pin "2") (pinfunction "2_2") (pintype "passive"))
      (node (ref "C9") (pin "2") (pinfunction "2_2") (pintype "passive"))
      (node (ref "D3") (pin "2") (pinfunction "GND_2") (pintype "bidirectional"))
      (node (ref "D4") (pin "1") (pinfunction "K_1") (pintype "bidirectional"))
      (node (ref "EPD_C1") (pin "1") (pinfunction "1_1") (pintype "passive"))
      (node (ref "EPD_C10") (pin "1") (pinfunction "1_1") (pintype "passive"))
      (node (ref "EPD_C11") (pin "1") (pinfunction "1_1") (pintype "passive"))
      (node (ref "EPD_C12") (pin "1") (pinfunction "1_1") (pintype "passive"))
      (node (ref "EPD_C2") (pin "1") (pinfunction "1_1") (pintype "passive"))
      (node (ref "EPD_C5") (pin "1") (pinfunction "1_1") (pintype "passive"))
      (node (ref "EPD_C6") (pin "1") (pinfunction "1_1") (pintype "passive"))
      (node (ref "EPD_C7") (pin "1") (pinfunction "1_1") (pintype "passive"))
      (node (ref "EPD_C8") (pin "1") (pinfunction "1_1") (pintype "passive"))
      (node (ref "EPD_C9") (pin "1") (pinfunction "1_1") (pintype "passive"))
      (node (ref "IC1") (pin "D2") (pinfunction "GND_D2") (pintype "bidirectional"))
      (node (ref "IC2") (pin "B1") (pinfunction "IN/TRIG_B1") (pintype "bidirectional"))
      (node (ref "IC2") (pin "B3") (pinfunction "GND_B3") (pintype "bidirectional"))
      (node (ref "IC3") (pin "8") (pinfunction "GNDIO_8") (pintype "bidirectional"))
      (node (ref "IC3") (pin "9") (pinfunction "GND_9") (pintype "bidirectional"))
      (node (ref "IC9") (pin "B1") (pinfunction "VSEL_B1") (pintype "bidirectional"))
      (node (ref "IC9") (pin "C1") (pinfunction "AGND_C1") (pintype "bidirectional"))
      (node (ref "IC9") (pin "C2") (pinfunction "PGND_1_C2") (pintype "bidirectional"))
      (node (ref "IC9") (pin "C3") (pinfunction "PGND_2_C3") (pintype "bidirectional"))
      (node (ref "J1") (pin "17") (pinfunction "17_17") (pintype "bidirectional"))
      (node (ref "J1") (pin "8") (pinfunction "8_8") (pintype "bidirectional"))
      (node (ref "J1") (pin "MP1") (pinfunction "MP1_MP1") (pintype "bidirectional"))
      (node (ref "J1") (pin "MP2") (pinfunction "MP2_MP2") (pintype "bidirectional"))
      (node (ref "J2") (pin "3") (pinfunction "3_3") (pintype "bidirectional"))
      (node (ref "J2") (pin "5") (pinfunction "5_5") (pintype "bidirectional"))
      (node (ref "J4") (pin "A12_B1") (pinfunction "GND_A12_B1") (pintype "power_in"))
      (node (ref "J4") (pin "A1_B12") (pinfunction "GND_A1_B12") (pintype "power_in"))
      (node (ref "J4") (pin "SH1") (pinfunction "SHIELD_SH1") (pintype "passive"))
      (node (ref "J4") (pin "SH2") (pinfunction "SHIELD_SH2") (pintype "passive"))
      (node (ref "J4") (pin "SH3") (pinfunction "SHIELD_SH3") (pintype "passive"))
      (node (ref "J4") (pin "SH4") (pinfunction "SHIELD_SH4") (pintype "passive"))
      (node (ref "R1_USB") (pin "1") (pinfunction "1_1") (pintype "bidirectional"))
      (node (ref "R2_EP_DR") (pin "1") (pinfunction "1_1") (pintype "bidirectional"))
      (node (ref "R2_USB") (pin "2") (pinfunction "2_2") (pintype "bidirectional"))
      (node (ref "R3") (pin "1") (pinfunction "1_1") (pintype "bidirectional"))
      (node (ref "R9") (pin "1") (pinfunction "1_1") (pintype "bidirectional"))
      (node (ref "R_TYPE_SEL") (pin "1") (pinfunction "1_1") (pintype "bidirectional"))
      (node (ref "SJ1") (pin "1") (pinfunction "1_1") (pintype "passive"))
      (node (ref "SW_DN") (pin "1") (pinfunction "1_1") (pintype "passive"))
      (node (ref "SW_ENT") (pin "1") (pinfunction "1_1") (pintype "passive"))
      (node (ref "SW_UP") (pin "1") (pinfunction "1_1") (pintype "passive"))
      (node (ref "TP_BAT_GND") (pin "TP") (pinfunction "TP_TP") (pintype "input"))
      (node (ref "TP_GND") (pin "TP") (pinfunction "TP_TP") (pintype "input"))
      (node (ref "U1") (pin "P$74") (pinfunction "VSS_PAD_P$74") (pintype "bidirectional"))
      (node (ref "U1") (pin "P$75") (pinfunction "VSS_PAD_P$75") (pintype "bidirectional"))
      (node (ref "U1") (pin "P$76") (pinfunction "VSS_PAD_P$76") (pintype "bidirectional"))
      (node (ref "U1") (pin "P$77") (pinfunction "VSS_PAD_P$77") (pintype "bidirectional"))
      (node (ref "U1") (pin "P$78") (pinfunction "VSS_PAD_P$78") (pintype "bidirectional"))
      (node (ref "U1") (pin "P$79") (pinfunction "VSS_PAD_P$79") (pintype "bidirectional"))
      (node (ref "U1") (pin "P$80") (pinfunction "VSS_PAD_P$80") (pintype "bidirectional"))
      (node (ref "U1") (pin "P$81") (pinfunction "VSS_PAD_P$81") (pintype "bidirectional"))
      (node (ref "U1") (pin "P$82") (pinfunction "VSS_PAD_P$82") (pintype "bidirectional"))
      (node (ref "U1") (pin "P$83") (pinfunction "VSS_PAD_P$83") (pintype "bidirectional"))
      (node (ref "U1") (pin "P$84") (pinfunction "VSS_PAD_P$84") (pintype "bidirectional"))
      (node (ref "U1") (pin "P$85") (pinfunction "VSS_PAD_P$85") (pintype "bidirectional"))
      (node (ref "U1") (pin "P$86") (pinfunction "VSS_PAD_P$86") (pintype "bidirectional"))
      (node (ref "U1") (pin "P$87") (pinfunction "VSS_PAD_P$87") (pintype "bidirectional"))
      (node (ref "U1") (pin "P$88") (pinfunction "VSS_PAD_P$88") (pintype "bidirectional"))
      (node (ref "U1") (pin "P$89") (pinfunction "VSS_PAD_P$89") (pintype "bidirectional"))
      (node (ref "U1") (pin "P$90") (pinfunction "VSS_PAD_P$90") (pintype "bidirectional"))
      (node (ref "U1") (pin "P$B7") (pinfunction "VSS_P$B7") (pintype "power_in"))
      (node (ref "U1") (pin "P$F23") (pinfunction "VSS_PA_P$F23") (pintype "bidirectional"))
      (node (ref "U3") (pin "1") (pinfunction "CTG_1") (pintype "power_in"))
      (node (ref "U3") (pin "4") (pinfunction "GND_4") (pintype "power_in"))
      (node (ref "U3") (pin "6") (pinfunction "QSTRT_6") (pintype "input"))
      (node (ref "U3") (pin "9") (pinfunction "EP_9") (pintype "power_in"))
      (node (ref "X1") (pin "2") (pinfunction "2_2") (pintype "passive"))
      (node (ref "X1") (pin "4") (pinfunction "4_4") (pintype "passive"))
    )
    (net (code "17") (name "HAPTIC_EN") (class "Default")
      (node (ref "IC2") (pin "A1") (pinfunction "EN_A1") (pintype "bidirectional"))
      (node (ref "U1") (pin "P$U1") (pinfunction "P0.12_P$U1") (pintype "bidirectional"))
    )
    (net (code "18") (name "IMU_INT1") (class "Default")
      (node (ref "IC3") (pin "5") (pinfunction "INT1_5") (pintype "bidirectional"))
      (node (ref "U1") (pin "P$N1") (pinfunction "P0.08_P$N1") (pintype "bidirectional"))
    )
    (net (code "19") (name "IMU_INT2") (class "Default")
      (node (ref "IC3") (pin "6") (pinfunction "INT2_6") (pintype "bidirectional"))
      (node (ref "U1") (pin "P$P2") (pinfunction "P1.08_P$P2") (pintype "bidirectional"))
    )
    (net (code "20") (name "LX1") (class "Default")
      (node (ref "IC9") (pin "B2") (pinfunction "SW1_1_B2") (pintype "bidirectional"))
      (node (ref "IC9") (pin "B3") (pinfunction "SW1_2_B3") (pintype "bidirectional"))
      (node (ref "L7") (pin "1") (pinfunction "1_1") (pintype "bidirectional"))
    )
    (net (code "21") (name "LX2") (class "Default")
      (node (ref "IC9") (pin "D2") (pinfunction "SW2_1_D2") (pintype "bidirectional"))
      (node (ref "IC9") (pin "D3") (pinfunction "SW2_2_D3") (pintype "bidirectional"))
      (node (ref "L7") (pin "2") (pinfunction "2_2") (pintype "bidirectional"))
    )
    (net (code "22") (name "MOSI") (class "Default")
      (node (ref "J1") (pin "14") (pinfunction "14_14") (pintype "bidirectional"))
      (node (ref "U1") (pin "P$B13") (pinfunction "P0.03/AIN1_P$B13") (pintype "bidirectional"))
    )
    (net (code "23") (name "Net-(ANT1-FEED)") (class "Default")
      (node (ref "ANT1") (pin "1") (pinfunction "FEED_1") (pintype "input"))
      (node (ref "C22") (pin "1") (pinfunction "1_1") (pintype "passive"))
      (node (ref "C4") (pin "1") (pinfunction "1_1") (pintype "passive"))
      (node (ref "L1") (pin "2") (pinfunction "2_2") (pintype "passive"))
    )
    (net (code "24") (name "Net-(D2-K)") (class "Default")
      (node (ref "C2-EP-DR") (pin "1") (pinfunction "1_1") (pintype "passive"))
      (node (ref "D2") (pin "1") (pinfunction "K_1") (pintype "bidirectional"))
      (node (ref "D4") (pin "2") (pinfunction "A_2") (pintype "bidirectional"))
    )
    (net (code "25") (name "Net-(D5-A)") (class "Default")
      (node (ref "C2-EP-DR") (pin "2") (pinfunction "2_2") (pintype "passive"))
      (node (ref "D5") (pin "2") (pinfunction "A_2") (pintype "bidirectional"))
      (node (ref "L5") (pin "2") (pinfunction "2_2") (pintype "passive"))
      (node (ref "Q3") (pin "3") (pinfunction "D_3") (pintype "bidirectional"))
    )
    (net (code "26") (name "Net-(EPD_C1-Pad2)") (class "Default")
      (node (ref "EPD_C1") (pin "2") (pinfunction "2_2") (pintype "passive"))
      (node (ref "J1") (pin "5") (pinfunction "5_5") (pintype "bidirectional"))
    )
    (net (code "27") (name "Net-(EPD_C2-Pad2)") (class "Default")
      (node (ref "EPD_C2") (pin "2") (pinfunction "2_2") (pintype "passive"))
      (node (ref "J1") (pin "4") (pinfunction "4_4") (pintype "bidirectional"))
    )
    (net (code "28") (name "Net-(EPD_C6-Pad2)") (class "Default")
      (node (ref "EPD_C6") (pin "2") (pinfunction "2_2") (pintype "passive"))
      (node (ref "J1") (pin "18") (pinfunction "18_18") (pintype "bidirectional"))
    )
    (net (code "29") (name "Net-(EPD_C7-Pad2)") (class "Default")
      (node (ref "EPD_C7") (pin "2") (pinfunction "2_2") (pintype "passive"))
      (node (ref "J1") (pin "19") (pinfunction "19_19") (pintype "bidirectional"))
    )
    (net (code "30") (name "Net-(EPD_C8-Pad2)") (class "Default")
      (node (ref "EPD_C8") (pin "2") (pinfunction "2_2") (pintype "passive"))
      (node (ref "J1") (pin "20") (pinfunction "20_20") (pintype "bidirectional"))
    )
    (net (code "31") (name "Net-(EPD_C10-Pad2)") (class "Default")
      (node (ref "EPD_C10") (pin "2") (pinfunction "2_2") (pintype "passive"))
      (node (ref "J1") (pin "22") (pinfunction "22_22") (pintype "bidirectional"))
    )
    (net (code "32") (name "Net-(EPD_C12-Pad2)") (class "Default")
      (node (ref "EPD_C12") (pin "2") (pinfunction "2_2") (pintype "passive"))
      (node (ref "J1") (pin "24") (pinfunction "24_24") (pintype "bidirectional"))
    )
    (net (code "33") (name "Net-(IC1-TS{slash}MR)") (class "Default")
      (node (ref "IC1") (pin "D1") (pinfunction "TS/MR_D1") (pintype "bidirectional"))
      (node (ref "R9") (pin "2") (pinfunction "2_2") (pintype "bidirectional"))
    )
    (net (code "34") (name "Net-(IC2-REG)") (class "Default")
      (node (ref "C32") (pin "2") (pinfunction "2_2") (pintype "passive"))
      (node (ref "IC2") (pin "A2") (pinfunction "REG_A2") (pintype "bidirectional"))
    )
    (net (code "35") (name "Net-(IC3-SDO)") (class "Default")
      (node (ref "IC3") (pin "1") (pinfunction "SDO_1") (pintype "bidirectional"))
      (node (ref "R3") (pin "2") (pinfunction "2_2") (pintype "bidirectional"))
    )
    (net (code "36") (name "Net-(IC9-SCL)") (class "Default")
      (node (ref "IC9") (pin "D1") (pinfunction "SCL_D1") (pintype "bidirectional"))
      (node (ref "R4") (pin "2") (pinfunction "2_2") (pintype "bidirectional"))
    )
    (net (code "37") (name "Net-(IC9-SDA)") (class "Default")
      (node (ref "IC9") (pin "E1") (pinfunction "SDA_E1") (pintype "bidirectional"))
      (node (ref "R2") (pin "2") (pinfunction "2_2") (pintype "bidirectional"))
    )
    (net (code "38") (name "Net-(J4-CC1)") (class "Default")
      (node (ref "J4") (pin "A5") (pinfunction "CC1_A5") (pintype "bidirectional"))
      (node (ref "R1_USB") (pin "2") (pinfunction "2_2") (pintype "bidirectional"))
    )
    (net (code "39") (name "Net-(J4-CC2)") (class "Default")
      (node (ref "J4") (pin "B5") (pinfunction "CC2_B5") (pintype "bidirectional"))
      (node (ref "R2_USB") (pin "1") (pinfunction "1_1") (pintype "bidirectional"))
    )
    (net (code "40") (name "Net-(L2-Pad2)") (class "Default")
      (node (ref "L2") (pin "2") (pinfunction "2_2") (pintype "passive"))
      (node (ref "L3") (pin "1") (pinfunction "1_1") (pintype "passive"))
    )
    (net (code "41") (name "Net-(R1_EP_DR-Pad1)") (class "Default")
      (node (ref "R1_EP_DR") (pin "1") (pinfunction "1_1") (pintype "bidirectional"))
      (node (ref "R_TYPE_SEL") (pin "2") (pinfunction "2_2") (pintype "bidirectional"))
      (node (ref "SJ1") (pin "2") (pinfunction "2_2") (pintype "passive"))
    )
    (net (code "42") (name "Net-(U1-ANT)") (class "Default")
      (node (ref "C3") (pin "1") (pinfunction "1_1") (pintype "passive"))
      (node (ref "L1") (pin "1") (pinfunction "1_1") (pintype "passive"))
      (node (ref "U1") (pin "P$H23") (pinfunction "ANT_P$H23") (pintype "bidirectional"))
    )
    (net (code "43") (name "Net-(U1-DCC)") (class "Default")
      (node (ref "L2") (pin "1") (pinfunction "1_1") (pintype "passive"))
      (node (ref "U1") (pin "P$B3") (pinfunction "DCC_P$B3") (pintype "output"))
    )
    (net (code "44") (name "Net-(U1-DEC2)") (class "Default")
      (node (ref "C13") (pin "1") (pinfunction "1_1") (pintype "passive"))
      (node (ref "U1") (pin "P$A18") (pinfunction "DEC2_P$A18") (pintype "bidirectional"))
    )
    (net (code "45") (name "Net-(U1-DEC3V3)") (class "Default")
      (node (ref "C20") (pin "1") (pinfunction "1_1") (pintype "passive"))
      (node (ref "U1") (pin "P$AC5") (pinfunction "DEC3V3_P$AC5") (pintype "bidirectional"))
    )
    (net (code "46") (name "Net-(U1-DEC5)") (class "Default")
      (node (ref "C9") (pin "1") (pinfunction "1_1") (pintype "passive"))
      (node (ref "U1") (pin "P$N24") (pinfunction "DEC5_P$N24") (pintype "bidirectional"))
    )
    (net (code "47") (name "Net-(U1-XC1)") (class "Default")
      (node (ref "C1") (pin "1") (pinfunction "1_1") (pintype "passive"))
      (node (ref "U1") (pin "P$B24") (pinfunction "XC1_P$B24") (pintype "input"))
      (node (ref "X1") (pin "1") (pinfunction "1_1") (pintype "passive"))
    )
    (net (code "48") (name "Net-(U1-XC2)") (class "Default")
      (node (ref "C2") (pin "1") (pinfunction "1_1") (pintype "passive"))
      (node (ref "U1") (pin "P$A23") (pinfunction "XC2_P$A23") (pintype "output"))
      (node (ref "X1") (pin "3") (pinfunction "3_3") (pintype "passive"))
    )
    (net (code "49") (name "OUT+") (class "Default")
      (node (ref "IC2") (pin "A3") (pinfunction "OUT+_A3") (pintype "bidirectional"))
      (node (ref "TP_OP") (pin "TP") (pinfunction "TP_TP") (pintype "input"))
    )
    (net (code "50") (name "OUT-") (class "Default")
      (node (ref "IC2") (pin "C3") (pinfunction "OUT-_C3") (pintype "bidirectional"))
      (node (ref "TP_ON") (pin "TP") (pinfunction "TP_TP") (pintype "input"))
    )
    (net (code "51") (name "P0.00{slash}XL1") (class "Default")
      (node (ref "C17") (pin "2") (pinfunction "2_2") (pintype "passive"))
      (node (ref "U1") (pin "P$D2") (pinfunction "P0.00/XL1_P$D2") (pintype "bidirectional"))
      (node (ref "X2") (pin "1") (pinfunction "1_1") (pintype "passive"))
    )
    (net (code "52") (name "P0.01{slash}XL2") (class "Default")
      (node (ref "C18") (pin "2") (pinfunction "2_2") (pintype "passive"))
      (node (ref "U1") (pin "P$F2") (pinfunction "P0.01/XL2_P$F2") (pintype "bidirectional"))
      (node (ref "X2") (pin "2") (pinfunction "2_2") (pintype "passive"))
    )
    (net (code "53") (name "P0.04") (class "Default")
      (node (ref "U1") (pin "P$J1") (pinfunction "P0.04/AIN2_P$J1") (pintype "bidirectional"))
    )
    (net (code "54") (name "P0.09") (class "Default")
      (node (ref "U1") (pin "P$L24") (pinfunction "P0.09/NFC1_P$L24") (pintype "bidirectional"))
    )
    (net (code "55") (name "P0.13") (class "Default")
      (node (ref "C30") (pin "2") (pinfunction "2_2") (pintype "passive"))
      (node (ref "R5") (pin "1") (pinfunction "1_1") (pintype "bidirectional"))
      (node (ref "SW_UP") (pin "2") (pinfunction "2_2") (pintype "passive"))
    )
    (net (code "56") (name "P0.14") (class "Default")
      (node (ref "C31") (pin "2") (pinfunction "2_2") (pintype "passive"))
      (node (ref "R8") (pin "1") (pinfunction "1_1") (pintype "bidirectional"))
      (node (ref "SW_ENT") (pin "2") (pinfunction "2_2") (pintype "passive"))
    )
    (net (code "57") (name "P0.19") (class "Default")
      (node (ref "U1") (pin "P$AC15") (pinfunction "P0.19_P$AC15") (pintype "bidirectional"))
    )
    (net (code "58") (name "P0.20") (class "Default")
      (node (ref "U1") (pin "P$AD16") (pinfunction "P0.20_P$AD16") (pintype "bidirectional"))
    )
    (net (code "59") (name "P0.21") (class "Default")
      (node (ref "U1") (pin "P$AC17") (pinfunction "P0.21_P$AC17") (pintype "bidirectional"))
    )
    (net (code "60") (name "P0.22") (class "Default")
      (node (ref "U1") (pin "P$AD18") (pinfunction "P0.22_P$AD18") (pintype "bidirectional"))
    )
    (net (code "61") (name "P0.23") (class "Default")
      (node (ref "U1") (pin "P$AC19") (pinfunction "P0.23_P$AC19") (pintype "bidirectional"))
    )
    (net (code "62") (name "P0.24") (class "Default")
      (node (ref "U1") (pin "P$AD20") (pinfunction "P0.24_P$AD20") (pintype "bidirectional"))
    )
    (net (code "63") (name "P0.25") (class "Default")
      (node (ref "U1") (pin "P$AC21") (pinfunction "P0.25_P$AC21") (pintype "bidirectional"))
    )
    (net (code "64") (name "P0.26") (class "Default")
      (node (ref "U1") (pin "P$G1") (pinfunction "P0.26_P$G1") (pintype "bidirectional"))
    )
    (net (code "65") (name "P0.27") (class "Default")
      (node (ref "U1") (pin "P$H2") (pinfunction "P0.27_P$H2") (pintype "bidirectional"))
    )
    (net (code "66") (name "P0.28") (class "Default")
      (node (ref "U1") (pin "P$B11") (pinfunction "P0.28/AIN4_P$B11") (pintype "bidirectional"))
    )
    (net (code "67") (name "P0.29") (class "Default")
      (node (ref "U1") (pin "P$A10") (pinfunction "P0.29/AIN5_P$A10") (pintype "bidirectional"))
    )
    (net (code "68") (name "P0.30") (class "Default")
      (node (ref "U1") (pin "P$B9") (pinfunction "P0.30/AIN6_P$B9") (pintype "bidirectional"))
    )
    (net (code "69") (name "P0.31") (class "Default")
      (node (ref "U1") (pin "P$A8") (pinfunction "P0.31/AIN7_P$A8") (pintype "bidirectional"))
    )
    (net (code "70") (name "P1.01") (class "Default")
      (node (ref "Q1") (pin "1") (pinfunction "G_1") (pintype "bidirectional"))
      (node (ref "R_PWR_EPD") (pin "1") (pinfunction "1_1") (pintype "bidirectional"))
      (node (ref "U1") (pin "P$Y23") (pinfunction "P1.01_P$Y23") (pintype "bidirectional"))
    )
    (net (code "71") (name "P1.02") (class "Default")
      (node (ref "C29") (pin "2") (pinfunction "2_2") (pintype "passive"))
      (node (ref "R7") (pin "1") (pinfunction "1_1") (pintype "bidirectional"))
      (node (ref "SW_DN") (pin "2") (pinfunction "2_2") (pintype "passive"))
      (node (ref "U1") (pin "P$W24") (pinfunction "P1.02_P$W24") (pintype "bidirectional"))
    )
    (net (code "72") (name "P1.03") (class "Default")
      (node (ref "U1") (pin "P$V23") (pinfunction "P1.03_P$V23") (pintype "bidirectional"))
    )
    (net (code "73") (name "P1.04") (class "Default")
      (node (ref "U1") (pin "P$U24") (pinfunction "P1.04_P$U24") (pintype "bidirectional"))
    )
    (net (code "74") (name "P1.05") (class "Default")
      (node (ref "U1") (pin "P$T23") (pinfunction "P1.05_P$T23") (pintype "bidirectional"))
    )
    (net (code "75") (name "P1.06") (class "Default")
      (node (ref "U1") (pin "P$R24") (pinfunction "P1.06_P$R24") (pintype "bidirectional"))
    )
    (net (code "76") (name "P1.07") (class "Default")
      (node (ref "U1") (pin "P$P23") (pinfunction "P1.07_P$P23") (pintype "bidirectional"))
    )
    (net (code "77") (name "P1.09") (class "Default")
      (node (ref "U1") (pin "P$R1") (pinfunction "P1.09_P$R1") (pintype "bidirectional"))
    )
    (net (code "78") (name "P1.10") (class "Default")
      (node (ref "U1") (pin "P$A20") (pinfunction "P1.10_P$A20") (pintype "bidirectional"))
    )
    (net (code "79") (name "P1.11") (class "Default")
      (node (ref "U1") (pin "P$B19") (pinfunction "P1.11_P$B19") (pintype "bidirectional"))
    )
    (net (code "80") (name "P1.12") (class "Default")
      (node (ref "U1") (pin "P$B17") (pinfunction "P1.12_P$B17") (pintype "bidirectional"))
    )
    (net (code "81") (name "P1.13") (class "Default")
      (node (ref "U1") (pin "P$A16") (pinfunction "P1.13_P$A16") (pintype "bidirectional"))
    )
    (net (code "82") (name "P1.14") (class "Default")
      (node (ref "U1") (pin "P$B15") (pinfunction "P1.14_P$B15") (pintype "bidirectional"))
    )
    (net (code "83") (name "P1.15") (class "Default")
      (node (ref "U1") (pin "P$A14") (pinfunction "P1.15_P$A14") (pintype "bidirectional"))
    )
    (net (code "84") (name "PMIC_INT") (class "Default")
      (node (ref "IC1") (pin "A1") (pinfunction "~{INT}_A1") (pintype "bidirectional"))
      (node (ref "U1") (pin "P$T2") (pinfunction "P0.11_P$T2") (pintype "bidirectional"))
    )
    (net (code "85") (name "PO.13") (class "Default")
      (node (ref "U1") (pin "P$AD8") (pinfunction "P0.13_P$AD8") (pintype "bidirectional"))
    )
    (net (code "86") (name "PO.14") (class "Default")
      (node (ref "U1") (pin "P$AC9") (pinfunction "P0.14_P$AC9") (pintype "bidirectional"))
    )
    (net (code "87") (name "PREVGH") (class "Default")
      (node (ref "D5") (pin "1") (pinfunction "K_1") (pintype "bidirectional"))
      (node (ref "EPD_C9") (pin "2") (pinfunction "2_2") (pintype "passive"))
      (node (ref "J1") (pin "21") (pinfunction "21_21") (pintype "bidirectional"))
    )
    (net (code "88") (name "PREVGL") (class "Default")
      (node (ref "D2") (pin "2") (pinfunction "A_2") (pintype "bidirectional"))
      (node (ref "EPD_C11") (pin "2") (pinfunction "2_2") (pintype "passive"))
      (node (ref "J1") (pin "23") (pinfunction "23_23") (pintype "bidirectional"))
    )
    (net (code "89") (name "RESE") (class "Default")
      (node (ref "J1") (pin "3") (pinfunction "3_3") (pintype "bidirectional"))
      (node (ref "Q3") (pin "2") (pinfunction "S_2") (pintype "bidirectional"))
      (node (ref "R1_EP_DR") (pin "2") (pinfunction "2_2") (pintype "bidirectional"))
    )
    (net (code "90") (name "RESET") (class "Default")
      (node (ref "J2") (pin "6") (pinfunction "6_6") (pintype "bidirectional"))
      (node (ref "TP_RESET") (pin "TP") (pinfunction "TP_TP") (pintype "input"))
      (node (ref "U1") (pin "P$AC13") (pinfunction "P0.18/RESET_P$AC13") (pintype "bidirectional"))
    )
    (net (code "91") (name "SCK") (class "Default")
      (node (ref "J1") (pin "13") (pinfunction "13_13") (pintype "bidirectional"))
      (node (ref "U1") (pin "P$A12") (pinfunction "P0.02/AIN0_P$A12") (pintype "bidirectional"))
    )
    (net (code "92") (name "SCL") (class "Default")
      (node (ref "IC1") (pin "B1") (pinfunction "SCL_B1") (pintype "bidirectional"))
      (node (ref "IC2") (pin "C1") (pinfunction "SCL_C1") (pintype "bidirectional"))
      (node (ref "IC3") (pin "12") (pinfunction "SCX_12") (pintype "bidirectional"))
      (node (ref "R17") (pin "2") (pinfunction "2_2") (pintype "bidirectional"))
      (node (ref "R4") (pin "1") (pinfunction "1_1") (pintype "bidirectional"))
      (node (ref "TP_SCL") (pin "TP") (pinfunction "TP_TP") (pintype "input"))
      (node (ref "U1") (pin "P$M2") (pinfunction "P0.07_P$M2") (pintype "bidirectional"))
      (node (ref "U3") (pin "7") (pinfunction "SCL_7") (pintype "input"))
    )
    (net (code "93") (name "SDA") (class "Default")
      (node (ref "IC1") (pin "C1") (pinfunction "SDA_C1") (pintype "bidirectional"))
      (node (ref "IC2") (pin "B2") (pinfunction "SDA_B2") (pintype "bidirectional"))
      (node (ref "IC3") (pin "2") (pinfunction "SDX_2") (pintype "bidirectional"))
      (node (ref "R18") (pin "2") (pinfunction "2_2") (pintype "bidirectional"))
      (node (ref "R2") (pin "1") (pinfunction "1_1") (pintype "bidirectional"))
      (node (ref "TP_SDA") (pin "TP") (pinfunction "TP_TP") (pintype "input"))
      (node (ref "U1") (pin "P$L1") (pinfunction "P0.06_P$L1") (pintype "bidirectional"))
      (node (ref "U3") (pin "8") (pinfunction "SDA_8") (pintype "bidirectional"))
    )
    (net (code "94") (name "SWDCLK") (class "Default")
      (node (ref "J2") (pin "4") (pinfunction "4_4") (pintype "bidirectional"))
      (node (ref "TP_SWDCLK") (pin "TP") (pinfunction "TP_TP") (pintype "input"))
      (node (ref "U1") (pin "P$AA24") (pinfunction "SWDCLK_P$AA24") (pintype "input"))
    )
    (net (code "95") (name "SWDIO") (class "Default")
      (node (ref "J2") (pin "2") (pinfunction "2_2") (pintype "bidirectional"))
      (node (ref "TP_SWDIO") (pin "TP") (pinfunction "TP_TP") (pintype "input"))
      (node (ref "U1") (pin "P$AC24") (pinfunction "SWDIO_P$AC24") (pintype "bidirectional"))
    )
    (net (code "96") (name "SWO") (class "Default")
      (node (ref "TP_SWO") (pin "TP") (pinfunction "TP_TP") (pintype "input"))
      (node (ref "U1") (pin "P$AD22") (pinfunction "P1.00_P$AD22") (pintype "bidirectional"))
    )
    (net (code "97") (name "VBAT") (class "Default")
      (node (ref "C27") (pin "2") (pinfunction "2_2") (pintype "passive"))
      (node (ref "C37") (pin "2") (pinfunction "2_2") (pintype "passive"))
      (node (ref "IC1") (pin "C2") (pinfunction "BAT_C2") (pintype "bidirectional"))
      (node (ref "TP_VBAT") (pin "TP") (pinfunction "TP_TP") (pintype "input"))
      (node (ref "U3") (pin "2") (pinfunction "CELL_2") (pintype "power_in"))
      (node (ref "U3") (pin "3") (pinfunction "VDD_3") (pintype "power_in"))
    )
    (net (code "98") (name "VBUS") (class "Default")
      (node (ref "C21") (pin "1") (pinfunction "1_1") (pintype "passive"))
      (node (ref "C38") (pin "2") (pinfunction "2_2") (pintype "passive"))
      (node (ref "C42") (pin "2") (pinfunction "2_2") (pintype "passive"))
      (node (ref "C43") (pin "1") (pinfunction "1_1") (pintype "passive"))
      (node (ref "D3") (pin "5") (pinfunction "VBUS_5") (pintype "bidirectional"))
      (node (ref "IC1") (pin "A2") (pinfunction "IN_A2") (pintype "bidirectional"))
      (node (ref "J4") (pin "A4_B9") (pinfunction "VBUS_A4_B9") (pintype "power_in"))
      (node (ref "J4") (pin "A9_B4") (pinfunction "VBUS_A9_B4") (pintype "power_in"))
      (node (ref "U1") (pin "P$AD2") (pinfunction "VBUS_P$AD2") (pintype "power_in"))
    )
    (net (code "99") (name "VREG") (class "Default")
      (node (ref "C23") (pin "2") (pinfunction "2_2") (pintype "passive"))
      (node (ref "C24") (pin "2") (pinfunction "2_2") (pintype "passive"))
      (node (ref "C39") (pin "1") (pinfunction "1_1") (pintype "passive"))
      (node (ref "IC1") (pin "B2") (pinfunction "SYS_B2") (pintype "bidirectional"))
      (node (ref "IC9") (pin "A1") (pinfunction "EN_A1") (pintype "bidirectional"))
      (node (ref "IC9") (pin "A2") (pinfunction "VIN_1_A2") (pintype "bidirectional"))
      (node (ref "IC9") (pin "A3") (pinfunction "VIN_2_A3") (pintype "bidirectional"))
      (node (ref "TP_VREG") (pin "TP") (pinfunction "TP_TP") (pintype "input"))
    )
    (net (code "100") (name "unconnected-(ANT1-NC-Pad2)") (class "Default")
      (node (ref "ANT1") (pin "2") (pinfunction "NC_2") (pintype "no_connect"))
    )
    (net (code "101") (name "unconnected-(IC3-ASCL-Pad11)") (class "Default")
      (node (ref "IC3") (pin "11") (pinfunction "ASCL_11") (pintype "bidirectional"))
    )
    (net (code "102") (name "unconnected-(IC3-ASDA-Pad4)") (class "Default")
      (node (ref "IC3") (pin "4") (pinfunction "ASDA_4") (pintype "bidirectional"))
    )
    (net (code "103") (name "unconnected-(J1-Pad1)") (class "Default")
      (node (ref "J1") (pin "1") (pinfunction "1_1") (pintype "bidirectional"))
    )
    (net (code "104") (name "unconnected-(J1-Pad6)") (class "Default")
      (node (ref "J1") (pin "6") (pinfunction "6_6") (pintype "bidirectional"))
    )
    (net (code "105") (name "unconnected-(J1-Pad7)") (class "Default")
      (node (ref "J1") (pin "7") (pinfunction "7_7") (pintype "bidirectional"))
    )
    (net (code "106") (name "unconnected-(J4-SBU1-PadA8)") (class "Default")
      (node (ref "J4") (pin "A8") (pinfunction "SBU1_A8") (pintype "bidirectional"))
    )
    (net (code "107") (name "unconnected-(J4-SBU2-PadB8)") (class "Default")
      (node (ref "J4") (pin "B8") (pinfunction "SBU2_B8") (pintype "bidirectional"))
    )
    (net (code "108") (name "unconnected-(U1-DCCH-PadP$AB2)") (class "Default")
      (node (ref "U1") (pin "P$AB2") (pinfunction "DCCH_P$AB2") (pintype "bidirectional"))
    )
  )
)
